# Atari_7800.net
KiCad netlist of a schematic drawn in EAGLE
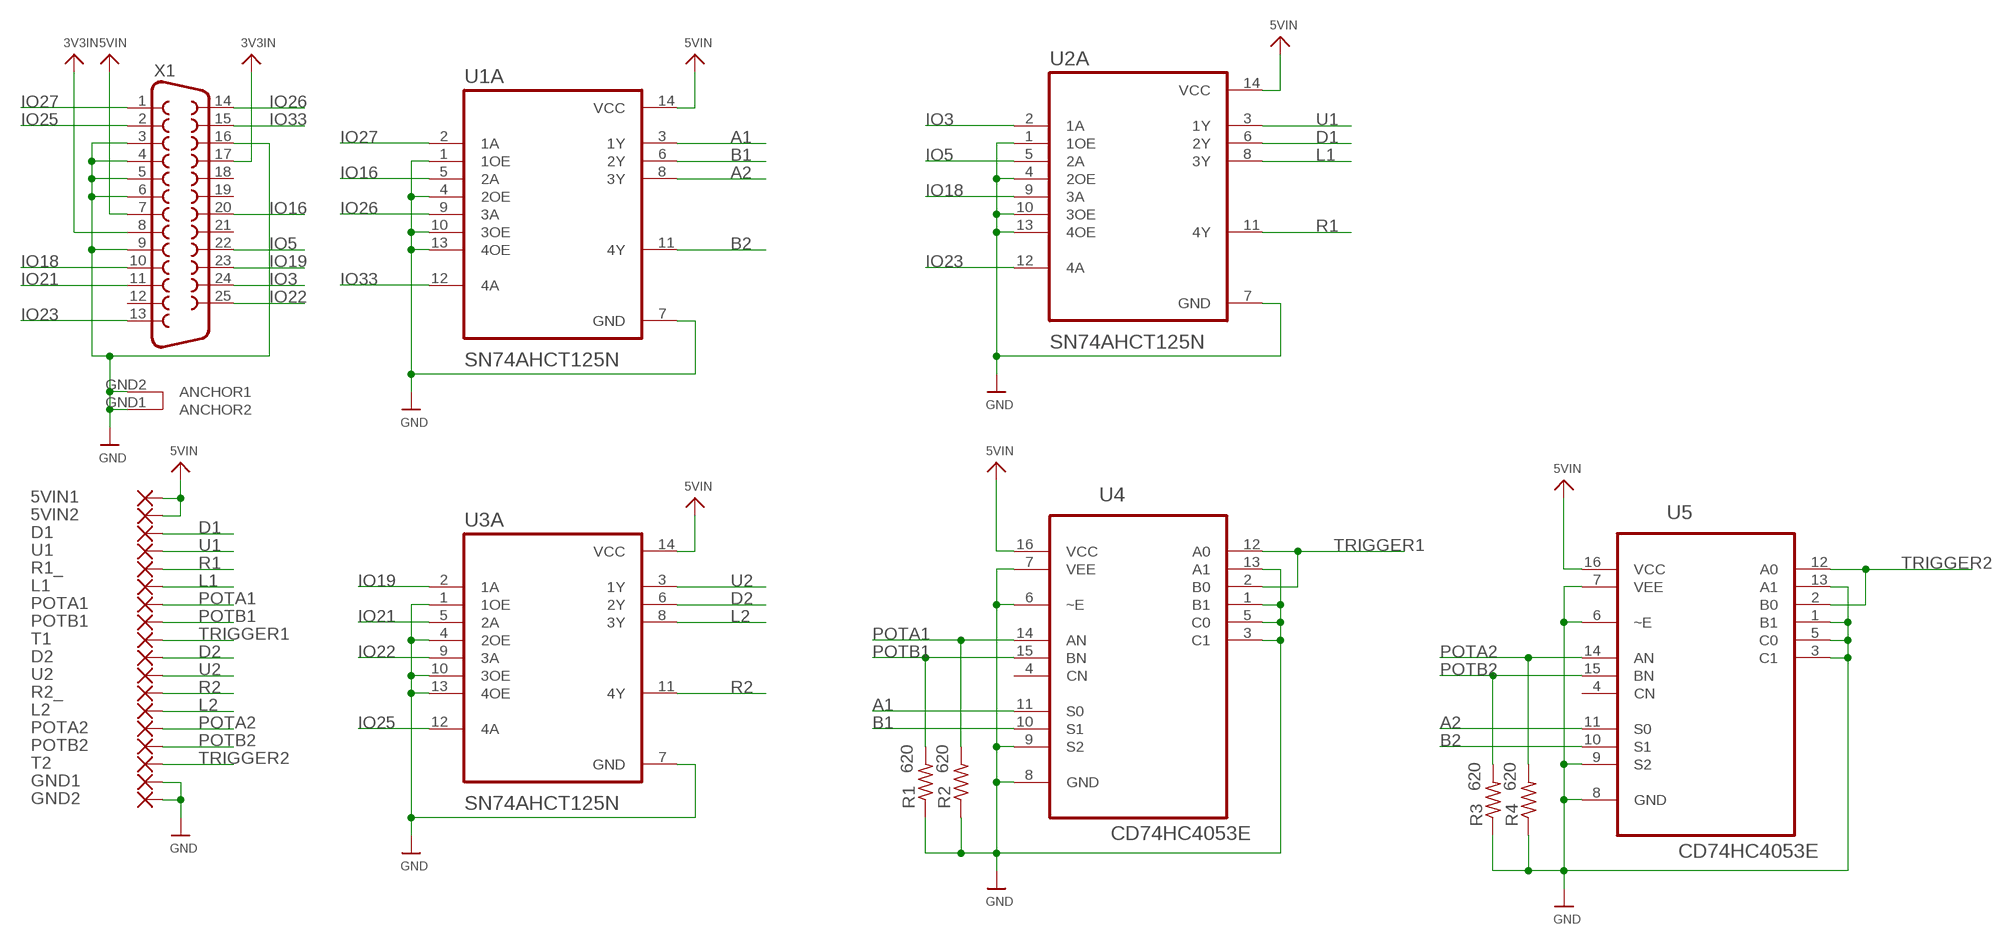
[diagram p0: schematic, sheet 1]

(export (version "E")
  (design (tool "Eeschema 10.0.6"))
  (components
    (comp (ref "5VIN1")
      (value "SMD5")
      (footprint "eagle-import:SMD2,54-5,08")
      (libsource (lib "eagle-import") (part "SMD5"))
    )
    (comp (ref "5VIN2")
      (value "SMD5")
      (footprint "eagle-import:SMD2,54-5,08")
      (libsource (lib "eagle-import") (part "SMD5"))
    )
    (comp (ref "D1")
      (value "SMD5")
      (footprint "eagle-import:SMD2,54-5,08")
      (libsource (lib "eagle-import") (part "SMD5"))
    )
    (comp (ref "D2")
      (value "SMD5")
      (footprint "eagle-import:SMD2,54-5,08")
      (libsource (lib "eagle-import") (part "SMD5"))
    )
    (comp (ref "GND1")
      (value "SMD5")
      (footprint "eagle-import:SMD2,54-5,08")
      (libsource (lib "eagle-import") (part "SMD5"))
    )
    (comp (ref "GND2")
      (value "SMD5")
      (footprint "eagle-import:SMD2,54-5,08")
      (libsource (lib "eagle-import") (part "SMD5"))
    )
    (comp (ref "L1")
      (value "SMD5")
      (footprint "eagle-import:SMD2,54-5,08")
      (libsource (lib "eagle-import") (part "SMD5"))
    )
    (comp (ref "L2")
      (value "SMD5")
      (footprint "eagle-import:SMD2,54-5,08")
      (libsource (lib "eagle-import") (part "SMD5"))
    )
    (comp (ref "POTA1")
      (value "SMD5")
      (footprint "eagle-import:SMD2,54-5,08")
      (libsource (lib "eagle-import") (part "SMD5"))
    )
    (comp (ref "POTA2")
      (value "SMD5")
      (footprint "eagle-import:SMD2,54-5,08")
      (libsource (lib "eagle-import") (part "SMD5"))
    )
    (comp (ref "POTB1")
      (value "SMD5")
      (footprint "eagle-import:SMD2,54-5,08")
      (libsource (lib "eagle-import") (part "SMD5"))
    )
    (comp (ref "POTB2")
      (value "SMD5")
      (footprint "eagle-import:SMD2,54-5,08")
      (libsource (lib "eagle-import") (part "SMD5"))
    )
    (comp (ref "R1")
      (value "620")
      (footprint "eagle-import:R1206")
      (libsource (lib "eagle-import") (part "R-US_R1206"))
    )
    (comp (ref "R1_")
      (value "SMD5")
      (footprint "eagle-import:SMD2,54-5,08")
      (libsource (lib "eagle-import") (part "SMD5"))
    )
    (comp (ref "R2")
      (value "620")
      (footprint "eagle-import:R1206")
      (libsource (lib "eagle-import") (part "R-US_R1206"))
    )
    (comp (ref "R2_")
      (value "SMD5")
      (footprint "eagle-import:SMD2,54-5,08")
      (libsource (lib "eagle-import") (part "SMD5"))
    )
    (comp (ref "R3")
      (value "620")
      (footprint "eagle-import:R1206")
      (libsource (lib "eagle-import") (part "R-US_R1206"))
    )
    (comp (ref "R4")
      (value "620")
      (footprint "eagle-import:R1206")
      (libsource (lib "eagle-import") (part "R-US_R1206"))
    )
    (comp (ref "T1")
      (value "SMD5")
      (footprint "eagle-import:SMD2,54-5,08")
      (libsource (lib "eagle-import") (part "SMD5"))
    )
    (comp (ref "T2")
      (value "SMD5")
      (footprint "eagle-import:SMD2,54-5,08")
      (libsource (lib "eagle-import") (part "SMD5"))
    )
    (comp (ref "U1")
      (value "SMD5")
      (footprint "eagle-import:SMD2,54-5,08")
      (libsource (lib "eagle-import") (part "SMD5"))
    )
    (comp (ref "U1A")
      (value "SN74AHCT125N")
      (footprint "eagle-import:DIP794W45P254L1969H508Q14")
      (fields (field (name "MF") "Texas Instruments"))
      (libsource (lib "eagle-import") (part "SN74AHCT125N"))
    )
    (comp (ref "U2")
      (value "SMD5")
      (footprint "eagle-import:SMD2,54-5,08")
      (libsource (lib "eagle-import") (part "SMD5"))
    )
    (comp (ref "U2A")
      (value "SN74AHCT125N")
      (footprint "eagle-import:DIP794W45P254L1969H508Q14")
      (fields (field (name "MF") "Texas Instruments"))
      (libsource (lib "eagle-import") (part "SN74AHCT125N"))
    )
    (comp (ref "U3A")
      (value "SN74AHCT125N")
      (footprint "eagle-import:DIP794W45P254L1969H508Q14")
      (fields (field (name "MF") "Texas Instruments"))
      (libsource (lib "eagle-import") (part "SN74AHCT125N"))
    )
    (comp (ref "U4")
      (value "CD74HC4053E")
      (footprint "eagle-import:DIP254P762X508-16")
      (fields (field (name "DIGI-KEY_PART_NUMBER") "296-9219-5-ND") (field (name "MF") "Texas"))
      (libsource (lib "eagle-import") (part "CD74HC4053E"))
    )
    (comp (ref "U5")
      (value "CD74HC4053E")
      (footprint "eagle-import:DIP254P762X508-16")
      (fields (field (name "DIGI-KEY_PART_NUMBER") "296-9219-5-ND") (field (name "MF") "Texas"))
      (libsource (lib "eagle-import") (part "CD74HC4053E"))
    )
    (comp (ref "X1")
      (value "DB25_FEMALEHP")
      (footprint "eagle-import:F25HP")
      (libsource (lib "eagle-import") (part "DB25_FEMALEHP"))
    )
  )
  (nets
    (net (code "1") (name "/A1") (class "Default")
      (node (ref "U1A") (pin "3") (pinfunction "1Y_3") (pintype "output"))
      (node (ref "U4") (pin "11") (pinfunction "S0_11") (pintype "input"))
    )
    (net (code "2") (name "/A2") (class "Default")
      (node (ref "U1A") (pin "8") (pinfunction "3Y_8") (pintype "output"))
      (node (ref "U5") (pin "11") (pinfunction "S0_11") (pintype "input"))
    )
    (net (code "3") (name "/B1") (class "Default")
      (node (ref "U1A") (pin "6") (pinfunction "2Y_6") (pintype "output"))
      (node (ref "U4") (pin "10") (pinfunction "S1_10") (pintype "input"))
    )
    (net (code "4") (name "/B2") (class "Default")
      (node (ref "U1A") (pin "11") (pinfunction "4Y_11") (pintype "output"))
      (node (ref "U5") (pin "10") (pinfunction "S1_10") (pintype "input"))
    )
    (net (code "5") (name "/D1") (class "Default")
      (node (ref "D1") (pin "1") (pinfunction "P_1") (pintype "passive"))
      (node (ref "U2A") (pin "6") (pinfunction "2Y_6") (pintype "output"))
    )
    (net (code "6") (name "/D2") (class "Default")
      (node (ref "D2") (pin "1") (pinfunction "P_1") (pintype "passive"))
      (node (ref "U3A") (pin "6") (pinfunction "2Y_6") (pintype "output"))
    )
    (net (code "7") (name "/IO3") (class "Default")
      (node (ref "U2A") (pin "2") (pinfunction "1A_2") (pintype "input"))
      (node (ref "X1") (pin "24") (pinfunction "24_24") (pintype "passive"))
    )
    (net (code "8") (name "/IO5") (class "Default")
      (node (ref "U2A") (pin "5") (pinfunction "2A_5") (pintype "input"))
      (node (ref "X1") (pin "22") (pinfunction "22_22") (pintype "passive"))
    )
    (net (code "9") (name "/IO16") (class "Default")
      (node (ref "U1A") (pin "5") (pinfunction "2A_5") (pintype "input"))
      (node (ref "X1") (pin "20") (pinfunction "20_20") (pintype "passive"))
    )
    (net (code "10") (name "/IO18") (class "Default")
      (node (ref "U2A") (pin "9") (pinfunction "3A_9") (pintype "input"))
      (node (ref "X1") (pin "10") (pinfunction "10_10") (pintype "passive"))
    )
    (net (code "11") (name "/IO19") (class "Default")
      (node (ref "U3A") (pin "2") (pinfunction "1A_2") (pintype "input"))
      (node (ref "X1") (pin "23") (pinfunction "23_23") (pintype "passive"))
    )
    (net (code "12") (name "/IO21") (class "Default")
      (node (ref "U3A") (pin "5") (pinfunction "2A_5") (pintype "input"))
      (node (ref "X1") (pin "11") (pinfunction "11_11") (pintype "passive"))
    )
    (net (code "13") (name "/IO22") (class "Default")
      (node (ref "U3A") (pin "9") (pinfunction "3A_9") (pintype "input"))
      (node (ref "X1") (pin "25") (pinfunction "25_25") (pintype "passive"))
    )
    (net (code "14") (name "/IO23") (class "Default")
      (node (ref "U2A") (pin "12") (pinfunction "4A_12") (pintype "bidirectional"))
      (node (ref "X1") (pin "13") (pinfunction "13_13") (pintype "passive"))
    )
    (net (code "15") (name "/IO25") (class "Default")
      (node (ref "U3A") (pin "12") (pinfunction "4A_12") (pintype "bidirectional"))
      (node (ref "X1") (pin "2") (pinfunction "2_2") (pintype "passive"))
    )
    (net (code "16") (name "/IO26") (class "Default")
      (node (ref "U1A") (pin "9") (pinfunction "3A_9") (pintype "input"))
      (node (ref "X1") (pin "14") (pinfunction "14_14") (pintype "passive"))
    )
    (net (code "17") (name "/IO27") (class "Default")
      (node (ref "U1A") (pin "2") (pinfunction "1A_2") (pintype "input"))
      (node (ref "X1") (pin "1") (pinfunction "1_1") (pintype "passive"))
    )
    (net (code "18") (name "/IO33") (class "Default")
      (node (ref "U1A") (pin "12") (pinfunction "4A_12") (pintype "bidirectional"))
      (node (ref "X1") (pin "15") (pinfunction "15_15") (pintype "passive"))
    )
    (net (code "19") (name "/L1") (class "Default")
      (node (ref "L1") (pin "1") (pinfunction "P_1") (pintype "passive"))
      (node (ref "U2A") (pin "8") (pinfunction "3Y_8") (pintype "output"))
    )
    (net (code "20") (name "/L2") (class "Default")
      (node (ref "L2") (pin "1") (pinfunction "P_1") (pintype "passive"))
      (node (ref "U3A") (pin "8") (pinfunction "3Y_8") (pintype "output"))
    )
    (net (code "21") (name "/POTA1") (class "Default")
      (node (ref "POTA1") (pin "1") (pinfunction "P_1") (pintype "passive"))
      (node (ref "R2") (pin "2") (pinfunction "2_2") (pintype "passive"))
      (node (ref "U4") (pin "14") (pinfunction "AN_14") (pintype "bidirectional"))
    )
    (net (code "22") (name "/POTA2") (class "Default")
      (node (ref "POTA2") (pin "1") (pinfunction "P_1") (pintype "passive"))
      (node (ref "R4") (pin "2") (pinfunction "2_2") (pintype "passive"))
      (node (ref "U5") (pin "14") (pinfunction "AN_14") (pintype "bidirectional"))
    )
    (net (code "23") (name "/POTB1") (class "Default")
      (node (ref "POTB1") (pin "1") (pinfunction "P_1") (pintype "passive"))
      (node (ref "R1") (pin "2") (pinfunction "2_2") (pintype "passive"))
      (node (ref "U4") (pin "15") (pinfunction "BN_15") (pintype "bidirectional"))
    )
    (net (code "24") (name "/POTB2") (class "Default")
      (node (ref "POTB2") (pin "1") (pinfunction "P_1") (pintype "passive"))
      (node (ref "R3") (pin "2") (pinfunction "2_2") (pintype "passive"))
      (node (ref "U5") (pin "15") (pinfunction "BN_15") (pintype "bidirectional"))
    )
    (net (code "25") (name "/R1") (class "Default")
      (node (ref "R1_") (pin "1") (pinfunction "P_1") (pintype "passive"))
      (node (ref "U2A") (pin "11") (pinfunction "4Y_11") (pintype "output"))
    )
    (net (code "26") (name "/R2") (class "Default")
      (node (ref "R2_") (pin "1") (pinfunction "P_1") (pintype "passive"))
      (node (ref "U3A") (pin "11") (pinfunction "4Y_11") (pintype "output"))
    )
    (net (code "27") (name "/TRIGGER1") (class "Default")
      (node (ref "T1") (pin "1") (pinfunction "P_1") (pintype "passive"))
      (node (ref "U4") (pin "12") (pinfunction "A0_12") (pintype "bidirectional"))
      (node (ref "U4") (pin "2") (pinfunction "B0_2") (pintype "bidirectional"))
    )
    (net (code "28") (name "/TRIGGER2") (class "Default")
      (node (ref "T2") (pin "1") (pinfunction "P_1") (pintype "passive"))
      (node (ref "U5") (pin "12") (pinfunction "A0_12") (pintype "bidirectional"))
      (node (ref "U5") (pin "2") (pinfunction "B0_2") (pintype "bidirectional"))
    )
    (net (code "29") (name "/U1") (class "Default")
      (node (ref "U1") (pin "1") (pinfunction "P_1") (pintype "passive"))
      (node (ref "U2A") (pin "3") (pinfunction "1Y_3") (pintype "output"))
    )
    (net (code "30") (name "/U2") (class "Default")
      (node (ref "U2") (pin "1") (pinfunction "P_1") (pintype "passive"))
      (node (ref "U3A") (pin "3") (pinfunction "1Y_3") (pintype "output"))
    )
    (net (code "31") (name "3V3IN") (class "Default")
      (node (ref "X1") (pin "17") (pinfunction "17_17") (pintype "passive"))
      (node (ref "X1") (pin "8") (pinfunction "8_8") (pintype "passive"))
    )
    (net (code "32") (name "5VIN") (class "Default")
      (node (ref "5VIN1") (pin "1") (pinfunction "P_1") (pintype "passive"))
      (node (ref "5VIN2") (pin "1") (pinfunction "P_1") (pintype "passive"))
      (node (ref "U1A") (pin "14") (pinfunction "VCC_14") (pintype "power_in"))
      (node (ref "U2A") (pin "14") (pinfunction "VCC_14") (pintype "power_in"))
      (node (ref "U3A") (pin "14") (pinfunction "VCC_14") (pintype "power_in"))
      (node (ref "U4") (pin "16") (pinfunction "VCC_16") (pintype "power_in"))
      (node (ref "U5") (pin "16") (pinfunction "VCC_16") (pintype "power_in"))
      (node (ref "X1") (pin "7") (pinfunction "7_7") (pintype "passive"))
    )
    (net (code "33") (name "GND") (class "Default")
      (node (ref "GND1") (pin "1") (pinfunction "P_1") (pintype "passive"))
      (node (ref "GND2") (pin "1") (pinfunction "P_1") (pintype "passive"))
      (node (ref "R1") (pin "1") (pinfunction "1_1") (pintype "passive"))
      (node (ref "R2") (pin "1") (pinfunction "1_1") (pintype "passive"))
      (node (ref "R3") (pin "1") (pinfunction "1_1") (pintype "passive"))
      (node (ref "R4") (pin "1") (pinfunction "1_1") (pintype "passive"))
      (node (ref "U1A") (pin "1") (pinfunction "1OE_1") (pintype "input"))
      (node (ref "U1A") (pin "10") (pinfunction "3OE_10") (pintype "input"))
      (node (ref "U1A") (pin "13") (pinfunction "4OE_13") (pintype "input"))
      (node (ref "U1A") (pin "4") (pinfunction "2OE_4") (pintype "input"))
      (node (ref "U1A") (pin "7") (pinfunction "GND_7") (pintype "power_in"))
      (node (ref "U2A") (pin "1") (pinfunction "1OE_1") (pintype "input"))
      (node (ref "U2A") (pin "10") (pinfunction "3OE_10") (pintype "input"))
      (node (ref "U2A") (pin "13") (pinfunction "4OE_13") (pintype "input"))
      (node (ref "U2A") (pin "4") (pinfunction "2OE_4") (pintype "input"))
      (node (ref "U2A") (pin "7") (pinfunction "GND_7") (pintype "power_in"))
      (node (ref "U3A") (pin "1") (pinfunction "1OE_1") (pintype "input"))
      (node (ref "U3A") (pin "10") (pinfunction "3OE_10") (pintype "input"))
      (node (ref "U3A") (pin "13") (pinfunction "4OE_13") (pintype "input"))
      (node (ref "U3A") (pin "4") (pinfunction "2OE_4") (pintype "input"))
      (node (ref "U3A") (pin "7") (pinfunction "GND_7") (pintype "power_in"))
      (node (ref "U4") (pin "1") (pinfunction "B1_1") (pintype "bidirectional"))
      (node (ref "U4") (pin "13") (pinfunction "A1_13") (pintype "bidirectional"))
      (node (ref "U4") (pin "3") (pinfunction "C1_3") (pintype "bidirectional"))
      (node (ref "U4") (pin "5") (pinfunction "C0_5") (pintype "bidirectional"))
      (node (ref "U4") (pin "6") (pinfunction "~{E}_6") (pintype "input"))
      (node (ref "U4") (pin "7") (pinfunction "VEE_7") (pintype "power_in"))
      (node (ref "U4") (pin "8") (pinfunction "GND_8") (pintype "passive"))
      (node (ref "U4") (pin "9") (pinfunction "S2_9") (pintype "input"))
      (node (ref "U5") (pin "1") (pinfunction "B1_1") (pintype "bidirectional"))
      (node (ref "U5") (pin "13") (pinfunction "A1_13") (pintype "bidirectional"))
      (node (ref "U5") (pin "3") (pinfunction "C1_3") (pintype "bidirectional"))
      (node (ref "U5") (pin "5") (pinfunction "C0_5") (pintype "bidirectional"))
      (node (ref "U5") (pin "6") (pinfunction "~{E}_6") (pintype "input"))
      (node (ref "U5") (pin "7") (pinfunction "VEE_7") (pintype "power_in"))
      (node (ref "U5") (pin "8") (pinfunction "GND_8") (pintype "passive"))
      (node (ref "U5") (pin "9") (pinfunction "S2_9") (pintype "input"))
      (node (ref "X1") (pin "16") (pinfunction "16_16") (pintype "passive"))
      (node (ref "X1") (pin "3") (pinfunction "3_3") (pintype "passive"))
      (node (ref "X1") (pin "4") (pinfunction "4_4") (pintype "passive"))
      (node (ref "X1") (pin "5") (pinfunction "5_5") (pintype "passive"))
      (node (ref "X1") (pin "6") (pinfunction "6_6") (pintype "passive"))
      (node (ref "X1") (pin "9") (pinfunction "9_9") (pintype "passive"))
      (node (ref "X1") (pin "GND1") (pinfunction "ANCHOR2_GND1") (pintype "bidirectional"))
      (node (ref "X1") (pin "GND2") (pinfunction "ANCHOR1_GND2") (pintype "bidirectional"))
    )
    (net (code "34") (name "unconnected-(U4-CN-Pad4)") (class "Default")
      (node (ref "U4") (pin "4") (pinfunction "CN_4") (pintype "passive"))
    )
    (net (code "35") (name "unconnected-(U5-CN-Pad4)") (class "Default")
      (node (ref "U5") (pin "4") (pinfunction "CN_4") (pintype "passive"))
    )
    (net (code "36") (name "unconnected-(X1-Pad12)") (class "Default")
      (node (ref "X1") (pin "12") (pinfunction "12_12") (pintype "passive"))
    )
    (net (code "37") (name "unconnected-(X1-Pad18)") (class "Default")
      (node (ref "X1") (pin "18") (pinfunction "18_18") (pintype "passive"))
    )
    (net (code "38") (name "unconnected-(X1-Pad19)") (class "Default")
      (node (ref "X1") (pin "19") (pinfunction "19_19") (pintype "passive"))
    )
    (net (code "39") (name "unconnected-(X1-Pad21)") (class "Default")
      (node (ref "X1") (pin "21") (pinfunction "21_21") (pintype "passive"))
    )
  )
)
